# Sheet1_MCU.net
KiCad netlist of a schematic drawn in Altium Designer
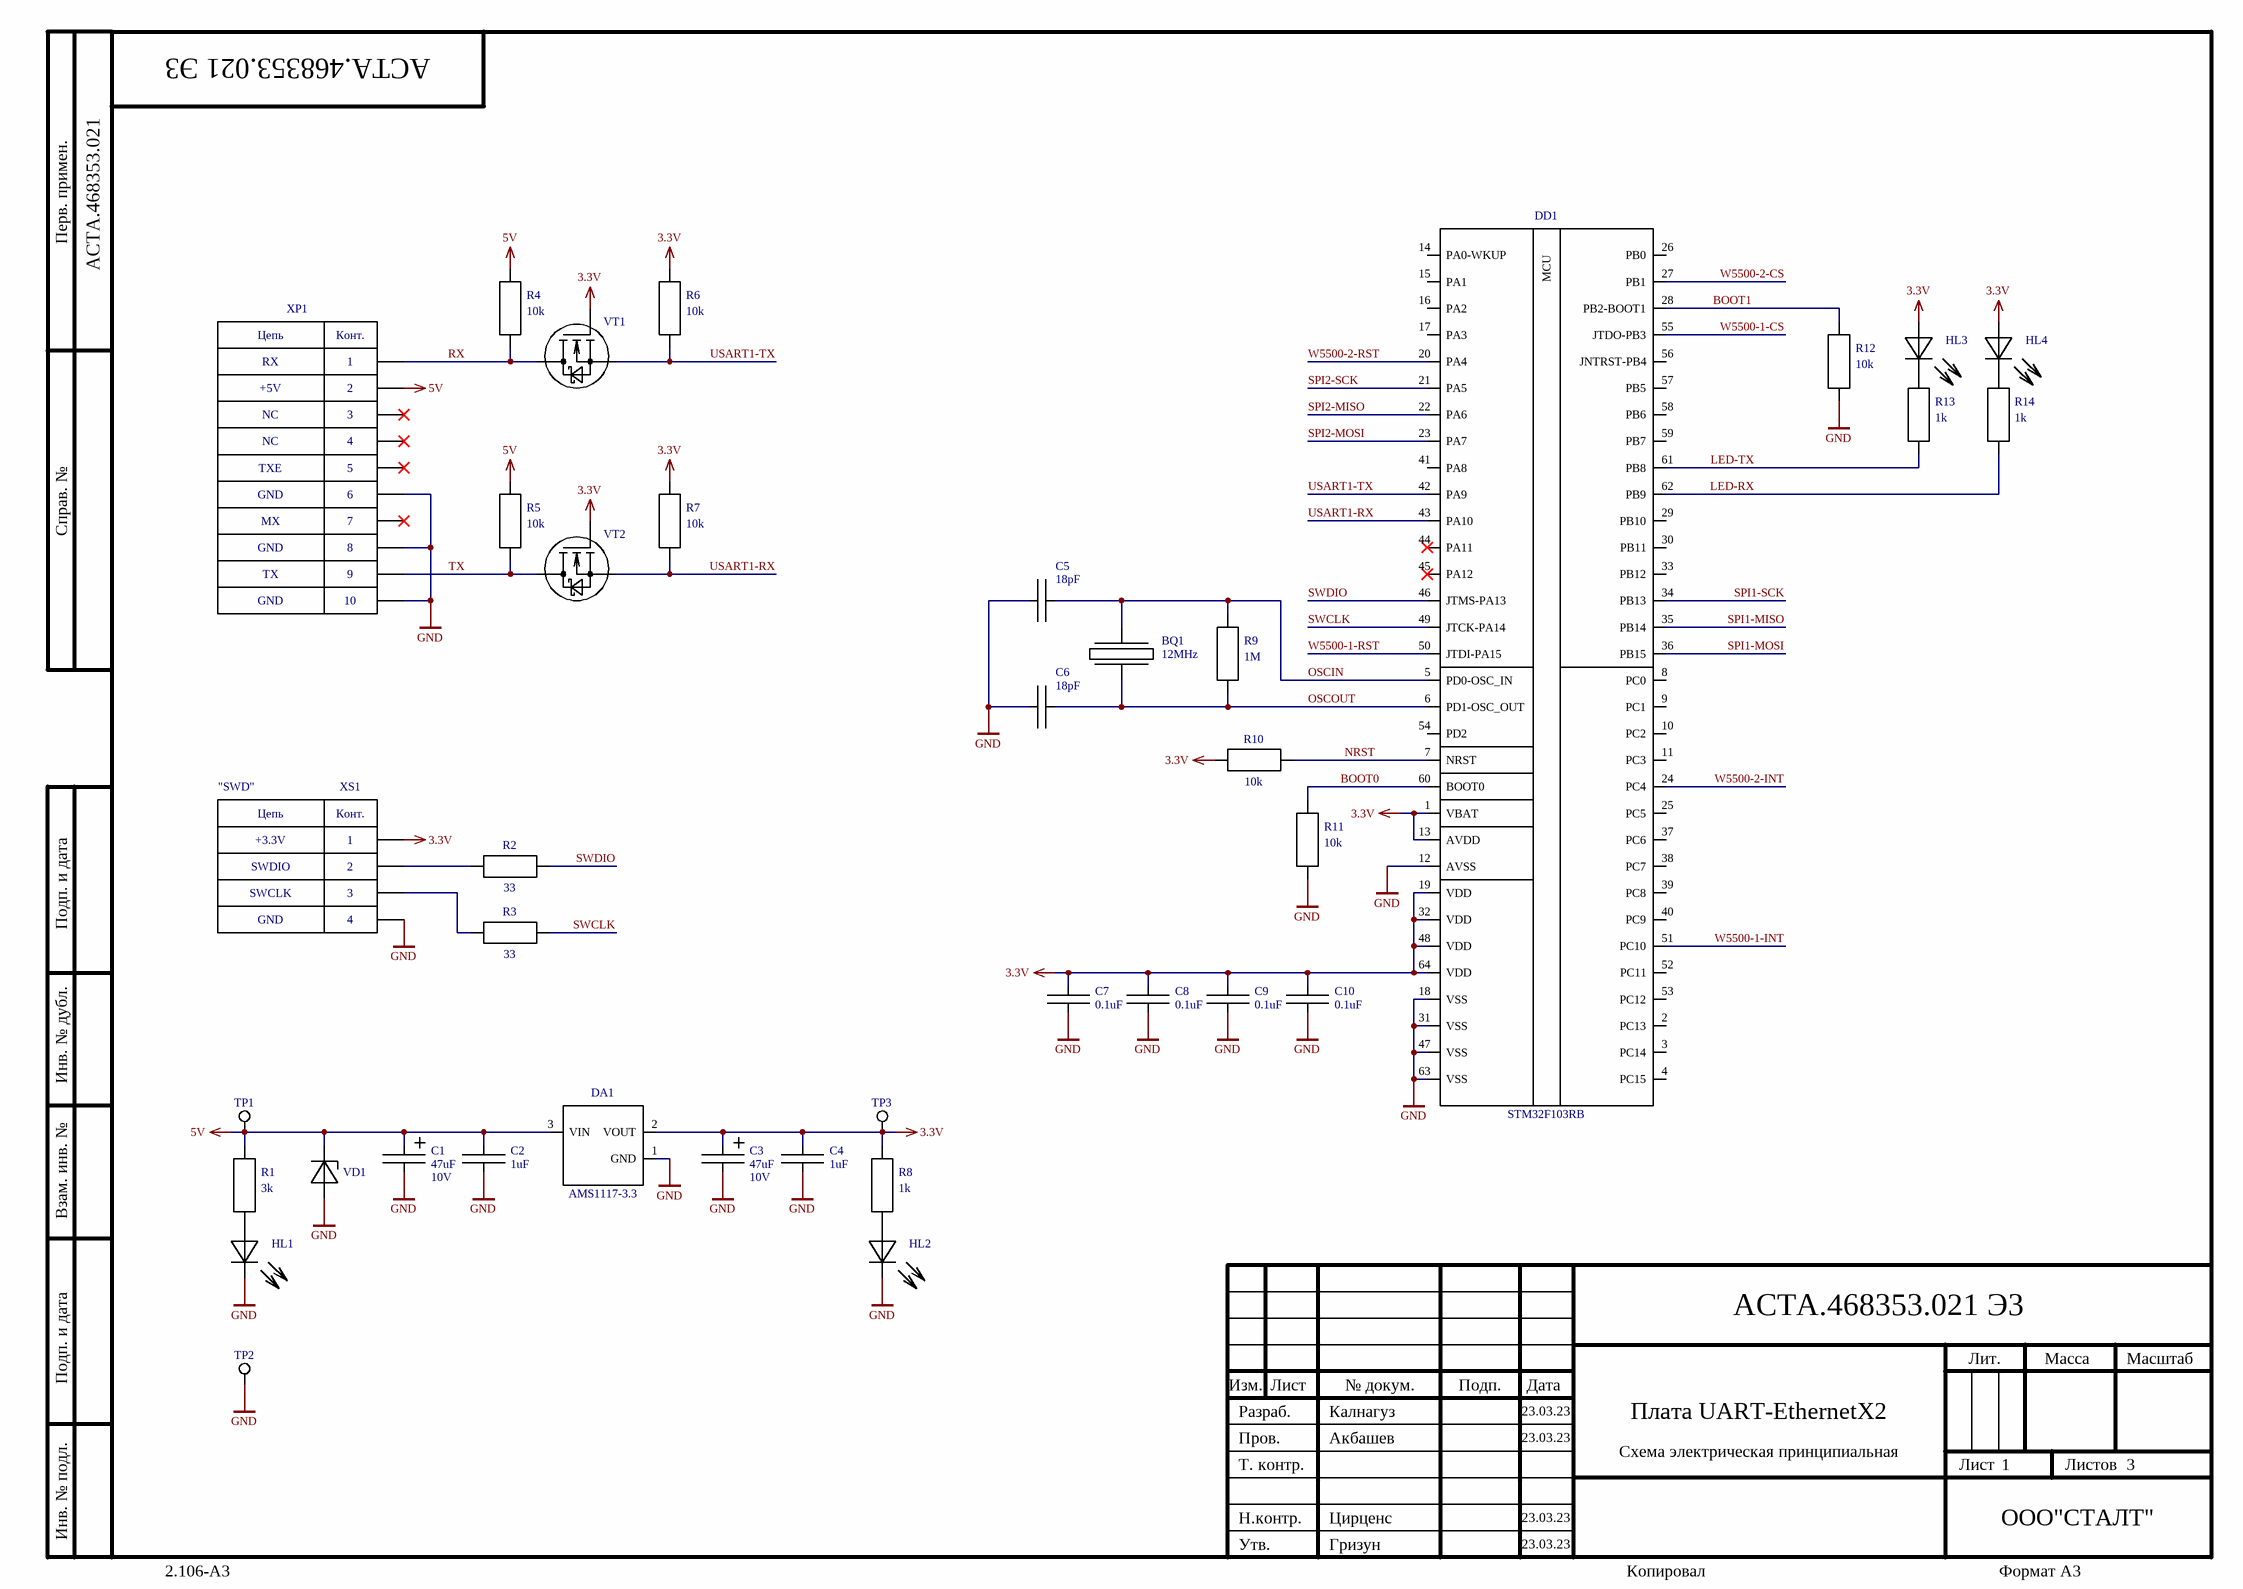
[diagram p0: Sheet1_MCU.SchDoc]

(export (version "E")
  (design (tool "Eeschema 10.0.6"))
  (components
    (comp (ref "BQ1")
      (value "12MHz")
      (footprint "HT-49S")
      (fields (field (name "Comment") "HT-49S_Rated"))
      (libsource (lib "Resonators") (part "HT-49S_Rated"))
    )
    (comp (ref "C1")
      (value "47uF")
      (footprint "CaseB_TantalumCap")
      (fields (field (name "VOLTAGE") "10V") (field (name "Comment") "CaseB_TantalumCap"))
      (libsource (lib "Tantalum_Capacitors") (part "CaseB_TantalumCap"))
    )
    (comp (ref "C2")
      (value "1uF")
      (footprint "CAP0805")
      (fields (field (name "Comment") "CAP0805_Rated"))
      (libsource (lib "Ceramic_Capacitors") (part "CAP0805_Rated"))
    )
    (comp (ref "C3")
      (value "47uF")
      (footprint "CaseB_TantalumCap")
      (fields (field (name "VOLTAGE") "10V") (field (name "Comment") "CaseB_TantalumCap"))
      (libsource (lib "Tantalum_Capacitors") (part "CaseB_TantalumCap"))
    )
    (comp (ref "C4")
      (value "1uF")
      (footprint "CAP0805")
      (fields (field (name "Comment") "CAP0805_Rated"))
      (libsource (lib "Ceramic_Capacitors") (part "CAP0805_Rated"))
    )
    (comp (ref "C5")
      (value "18pF")
      (footprint "CAP0805")
      (fields (field (name "Comment") "CAP0805_Rated"))
      (libsource (lib "Ceramic_Capacitors") (part "CAP0805_Rated"))
    )
    (comp (ref "C6")
      (value "18pF")
      (footprint "CAP0805")
      (fields (field (name "Comment") "CAP0805_Rated"))
      (libsource (lib "Ceramic_Capacitors") (part "CAP0805_Rated"))
    )
    (comp (ref "C7")
      (value "0.1uF")
      (footprint "CAP0805")
      (fields (field (name "Comment") "CAP0805_Rated"))
      (libsource (lib "Ceramic_Capacitors") (part "CAP0805_Rated"))
    )
    (comp (ref "C8")
      (value "0.1uF")
      (footprint "CAP0805")
      (fields (field (name "Comment") "CAP0805_Rated"))
      (libsource (lib "Ceramic_Capacitors") (part "CAP0805_Rated"))
    )
    (comp (ref "C9")
      (value "0.1uF")
      (footprint "CAP0805")
      (fields (field (name "Comment") "CAP0805_Rated"))
      (libsource (lib "Ceramic_Capacitors") (part "CAP0805_Rated"))
    )
    (comp (ref "C10")
      (value "0.1uF")
      (footprint "CAP0805")
      (fields (field (name "Comment") "CAP0805_Rated"))
      (libsource (lib "Ceramic_Capacitors") (part "CAP0805_Rated"))
    )
    (comp (ref "DA1")
      (value "AMS1117-3.3")
      (footprint "SOT-223")
      (description "Fixed Voltage 3.3V 1A Low Dropout Voltage Regulator")
      (libsource (lib "Power_Management_ICs") (part "AMS1117-3.3"))
    )
    (comp (ref "DD1")
      (value "STM32F103RB")
      (footprint "LQFP-64")
      (description "ARM Cortex-M3 MCU")
      (libsource (lib "MCU") (part "STM32F103RB"))
    )
    (comp (ref "HL1")
      (value "KPTD-3216MGC")
      (footprint "KPTD-3216 Green")
      (description "3.2x1.6mm SMD LED Mega Green")
      (libsource (lib "LEDs_SMD") (part "KPTD-3216MGC"))
    )
    (comp (ref "HL2")
      (value "KPTD-3216MGC")
      (footprint "KPTD-3216 Green")
      (description "3.2x1.6mm SMD LED Mega Green")
      (libsource (lib "LEDs_SMD") (part "KPTD-3216MGC"))
    )
    (comp (ref "HL3")
      (value "KPTD-3216MGC")
      (footprint "KPTD-3216 Green")
      (description "3.2x1.6mm SMD LED Mega Green")
      (libsource (lib "LEDs_SMD") (part "KPTD-3216MGC"))
    )
    (comp (ref "HL4")
      (value "KPTD-3216SYC")
      (footprint "KPTD-3216 Yellow")
      (description "3.2x1.6mm SMD LED Super Bright Yellow")
      (libsource (lib "LEDs_SMD") (part "KPTD-3216SYC"))
    )
    (comp (ref "R1")
      (value "3k")
      (footprint "RES0805")
      (fields (field (name "TOLERANCE") "5%") (field (name "Comment") "RES0805_Rated"))
      (libsource (lib "Resistors") (part "RES0805_Rated"))
    )
    (comp (ref "R2")
      (value "33")
      (footprint "RES0805")
      (fields (field (name "TOLERANCE") "5%") (field (name "Comment") "RES0805_Rated"))
      (libsource (lib "") (part "RES0805_Rated_1"))
    )
    (comp (ref "R3")
      (value "33")
      (footprint "RES0805")
      (fields (field (name "TOLERANCE") "5%") (field (name "Comment") "RES0805_Rated"))
      (libsource (lib "") (part "RES0805_Rated_1"))
    )
    (comp (ref "R4")
      (value "10k")
      (footprint "RES0805")
      (fields (field (name "TOLERANCE") "5%") (field (name "Comment") "RES0805_Rated"))
      (libsource (lib "Resistors") (part "RES0805_Rated"))
    )
    (comp (ref "R5")
      (value "10k")
      (footprint "RES0805")
      (fields (field (name "TOLERANCE") "5%") (field (name "Comment") "RES0805_Rated"))
      (libsource (lib "Resistors") (part "RES0805_Rated"))
    )
    (comp (ref "R6")
      (value "10k")
      (footprint "RES0805")
      (fields (field (name "TOLERANCE") "5%") (field (name "Comment") "RES0805_Rated"))
      (libsource (lib "Resistors") (part "RES0805_Rated"))
    )
    (comp (ref "R7")
      (value "10k")
      (footprint "RES0805")
      (fields (field (name "TOLERANCE") "5%") (field (name "Comment") "RES0805_Rated"))
      (libsource (lib "Resistors") (part "RES0805_Rated"))
    )
    (comp (ref "R8")
      (value "1k")
      (footprint "RES0805")
      (fields (field (name "TOLERANCE") "5%") (field (name "Comment") "RES0805_Rated"))
      (libsource (lib "Resistors") (part "RES0805_Rated"))
    )
    (comp (ref "R9")
      (value "1M")
      (footprint "RES0805")
      (fields (field (name "TOLERANCE") "5%") (field (name "Comment") "RES0805_Rated"))
      (libsource (lib "Resistors") (part "RES0805_Rated"))
    )
    (comp (ref "R10")
      (value "10k")
      (footprint "RES0805")
      (fields (field (name "TOLERANCE") "5%") (field (name "Comment") "RES0805_Rated"))
      (libsource (lib "") (part "RES0805_Rated_1"))
    )
    (comp (ref "R11")
      (value "10k")
      (footprint "RES0805")
      (fields (field (name "TOLERANCE") "5%") (field (name "Comment") "RES0805_Rated"))
      (libsource (lib "Resistors") (part "RES0805_Rated"))
    )
    (comp (ref "R12")
      (value "10k")
      (footprint "RES0805")
      (fields (field (name "TOLERANCE") "5%") (field (name "Comment") "RES0805_Rated"))
      (libsource (lib "Resistors") (part "RES0805_Rated"))
    )
    (comp (ref "R13")
      (value "1k")
      (footprint "RES0805")
      (fields (field (name "TOLERANCE") "5%") (field (name "Comment") "RES0805_Rated"))
      (libsource (lib "Resistors") (part "RES0805_Rated"))
    )
    (comp (ref "R14")
      (value "1k")
      (footprint "RES0805")
      (fields (field (name "TOLERANCE") "5%") (field (name "Comment") "RES0805_Rated"))
      (libsource (lib "Resistors") (part "RES0805_Rated"))
    )
    (comp (ref "TP1")
      (value "TestPad")
      (footprint "PAD-TH-OCT1x1-0.5")
      (description "TestPoint on PCB")
      (libsource (lib "Connectors") (part "TestPad"))
    )
    (comp (ref "TP2")
      (value "TestPad")
      (footprint "PAD-TH-OCT1x1-0.5")
      (description "TestPoint on PCB")
      (libsource (lib "Connectors") (part "TestPad"))
    )
    (comp (ref "TP3")
      (value "TestPad")
      (footprint "PAD-TH-OCT1x1-0.5")
      (description "TestPoint on PCB")
      (libsource (lib "Connectors") (part "TestPad"))
    )
    (comp (ref "VD1")
      (value "SMAJ5.0A")
      (footprint "SMA (DO-214AC)")
      (description "5Vr 400W 43.5A UniDirectional TVS")
      (libsource (lib "TVS_Diodes") (part "SMAJ5.0A"))
    )
    (comp (ref "VT1")
      (value "BSS138")
      (footprint "SOT-23")
      (description "Small Signal N-Channel MOSFET 50V 220mA")
      (libsource (lib "MOSFETs") (part "BSS138"))
    )
    (comp (ref "VT2")
      (value "BSS138")
      (footprint "SOT-23")
      (description "Small Signal N-Channel MOSFET 50V 220mA")
      (libsource (lib "MOSFETs") (part "BSS138"))
    )
    (comp (ref "XP1")
      (value "IDC-10MS")
      (footprint "IDC-10MS pad1.6x2.0")
      (description "Box Header Pitch 2.54mm")
      (fields
        (field (name "CIRCUIT7") "MX")
        (field (name "CIRCUIT8") "GND")
        (field (name "CIRCUIT9") "TX")
        (field (name "CIRCUIT10") "GND")
        (field (name "CIRCUIT6") "GND")
        (field (name "CIRCUIT4") "NC")
        (field (name "CIRCUIT5") "TXE")
        (field (name "CIRCUIT3") "NC")
        (field (name "CIRCUIT2") "+5V")
        (field (name "CIRCUIT1") "RX")
      )
      (libsource (lib "Connectors") (part "IDC-10MS"))
    )
    (comp (ref "XS1")
      (value "PBS-4")
      (footprint "PBS-4")
      (description "Female Header Pitch 2.54mm")
      (fields
        (field (name "CIRCUIT4") "GND")
        (field (name "CIRCUIT3") "SWCLK")
        (field (name "CIRCUIT1") "+3.3V")
        (field (name "CIRCUIT2") "SWDIO")
        (field (name "LABEL") "\"SWD\"")
      )
      (libsource (lib "Connectors") (part "PBS-4"))
    )
  )
  (nets
    (net (code "1") (name "/BOOT0") (class "Default")
      (node (ref "DD1") (pin "60") (pinfunction "BOOT0_60") (pintype "power_in"))
      (node (ref "R11") (pin "2") (pinfunction "2_2") (pintype "passive"))
    )
    (net (code "2") (name "/BOOT1") (class "Default")
      (node (ref "DD1") (pin "28") (pinfunction "PB2-BOOT1_28") (pintype "bidirectional"))
      (node (ref "R12") (pin "2") (pinfunction "2_2") (pintype "passive"))
    )
    (net (code "3") (name "/LED-RX") (class "Default")
      (node (ref "DD1") (pin "62") (pinfunction "PB9_62") (pintype "bidirectional"))
      (node (ref "R14") (pin "1") (pinfunction "1_1") (pintype "passive"))
    )
    (net (code "4") (name "/LED-TX") (class "Default")
      (node (ref "DD1") (pin "61") (pinfunction "PB8_61") (pintype "bidirectional"))
      (node (ref "R13") (pin "1") (pinfunction "1_1") (pintype "passive"))
    )
    (net (code "5") (name "/NRST") (class "Default")
      (node (ref "DD1") (pin "7") (pinfunction "NRST_7") (pintype "bidirectional"))
      (node (ref "R10") (pin "2") (pinfunction "2_2") (pintype "passive"))
    )
    (net (code "6") (name "/OSCIN") (class "Default")
      (node (ref "BQ1") (pin "1") (pinfunction "1_1") (pintype "passive"))
      (node (ref "C5") (pin "2") (pinfunction "2_2") (pintype "passive"))
      (node (ref "DD1") (pin "5") (pinfunction "PD0-OSC_IN_5") (pintype "bidirectional"))
      (node (ref "R9") (pin "2") (pinfunction "2_2") (pintype "passive"))
    )
    (net (code "7") (name "/OSCOUT") (class "Default")
      (node (ref "BQ1") (pin "2") (pinfunction "2_2") (pintype "passive"))
      (node (ref "C6") (pin "2") (pinfunction "2_2") (pintype "passive"))
      (node (ref "DD1") (pin "6") (pinfunction "PD1-OSC_OUT_6") (pintype "bidirectional"))
      (node (ref "R9") (pin "1") (pinfunction "1_1") (pintype "passive"))
    )
    (net (code "8") (name "/RX") (class "Default")
      (node (ref "R4") (pin "1") (pinfunction "1_1") (pintype "passive"))
      (node (ref "VT1") (pin "2") (pinfunction "D_2") (pintype "passive"))
      (node (ref "XP1") (pin "1") (pinfunction "1_1") (pintype "passive"))
    )
    (net (code "9") (name "/SPI1-MISO") (class "Default")
      (node (ref "DD1") (pin "35") (pinfunction "PB14_35") (pintype "bidirectional"))
    )
    (net (code "10") (name "/SPI1-MOSI") (class "Default")
      (node (ref "DD1") (pin "36") (pinfunction "PB15_36") (pintype "bidirectional"))
    )
    (net (code "11") (name "/SPI1-SCK") (class "Default")
      (node (ref "DD1") (pin "34") (pinfunction "PB13_34") (pintype "bidirectional"))
    )
    (net (code "12") (name "/SPI2-MISO") (class "Default")
      (node (ref "DD1") (pin "22") (pinfunction "PA6_22") (pintype "bidirectional"))
    )
    (net (code "13") (name "/SPI2-MOSI") (class "Default")
      (node (ref "DD1") (pin "23") (pinfunction "PA7_23") (pintype "bidirectional"))
    )
    (net (code "14") (name "/SPI2-SCK") (class "Default")
      (node (ref "DD1") (pin "21") (pinfunction "PA5_21") (pintype "bidirectional"))
    )
    (net (code "15") (name "/SWCLK") (class "Default")
      (node (ref "DD1") (pin "49") (pinfunction "JTCK-PA14_49") (pintype "bidirectional"))
      (node (ref "R3") (pin "2") (pinfunction "2_2") (pintype "passive"))
    )
    (net (code "16") (name "/SWDIO") (class "Default")
      (node (ref "DD1") (pin "46") (pinfunction "JTMS-PA13_46") (pintype "bidirectional"))
      (node (ref "R2") (pin "2") (pinfunction "2_2") (pintype "passive"))
    )
    (net (code "17") (name "/TX") (class "Default")
      (node (ref "R5") (pin "1") (pinfunction "1_1") (pintype "passive"))
      (node (ref "VT2") (pin "2") (pinfunction "D_2") (pintype "passive"))
      (node (ref "XP1") (pin "9") (pinfunction "9_9") (pintype "passive"))
    )
    (net (code "18") (name "/USART1-RX") (class "Default")
      (node (ref "DD1") (pin "43") (pinfunction "PA10_43") (pintype "bidirectional"))
      (node (ref "R7") (pin "1") (pinfunction "1_1") (pintype "passive"))
      (node (ref "VT2") (pin "3") (pinfunction "S_3") (pintype "passive"))
    )
    (net (code "19") (name "/USART1-TX") (class "Default")
      (node (ref "DD1") (pin "42") (pinfunction "PA9_42") (pintype "bidirectional"))
      (node (ref "R6") (pin "1") (pinfunction "1_1") (pintype "passive"))
      (node (ref "VT1") (pin "3") (pinfunction "S_3") (pintype "passive"))
    )
    (net (code "20") (name "/W5500-1-CS") (class "Default")
      (node (ref "DD1") (pin "55") (pinfunction "JTDO-PB3_55") (pintype "bidirectional"))
    )
    (net (code "21") (name "/W5500-1-INT") (class "Default")
      (node (ref "DD1") (pin "51") (pinfunction "PC10_51") (pintype "bidirectional"))
    )
    (net (code "22") (name "/W5500-1-RST") (class "Default")
      (node (ref "DD1") (pin "50") (pinfunction "JTDI-PA15_50") (pintype "bidirectional"))
    )
    (net (code "23") (name "/W5500-2-CS") (class "Default")
      (node (ref "DD1") (pin "27") (pinfunction "PB1_27") (pintype "bidirectional"))
    )
    (net (code "24") (name "/W5500-2-INT") (class "Default")
      (node (ref "DD1") (pin "24") (pinfunction "PC4_24") (pintype "bidirectional"))
    )
    (net (code "25") (name "/W5500-2-RST") (class "Default")
      (node (ref "DD1") (pin "20") (pinfunction "PA4_20") (pintype "bidirectional"))
    )
    (net (code "26") (name "3.3V") (class "Default")
      (node (ref "C10") (pin "1") (pinfunction "1_1") (pintype "passive"))
      (node (ref "C3") (pin "1") (pinfunction "+_1") (pintype "passive"))
      (node (ref "C4") (pin "1") (pinfunction "1_1") (pintype "passive"))
      (node (ref "C7") (pin "1") (pinfunction "1_1") (pintype "passive"))
      (node (ref "C8") (pin "1") (pinfunction "1_1") (pintype "passive"))
      (node (ref "C9") (pin "1") (pinfunction "1_1") (pintype "passive"))
      (node (ref "DA1") (pin "2") (pinfunction "VOUT_2") (pintype "power_in"))
      (node (ref "DD1") (pin "1") (pinfunction "VBAT_1") (pintype "power_in"))
      (node (ref "DD1") (pin "13") (pinfunction "AVDD_13") (pintype "power_in"))
      (node (ref "DD1") (pin "19") (pinfunction "VDD_19") (pintype "power_in"))
      (node (ref "DD1") (pin "32") (pinfunction "VDD_32") (pintype "power_in"))
      (node (ref "DD1") (pin "48") (pinfunction "VDD_48") (pintype "power_in"))
      (node (ref "DD1") (pin "64") (pinfunction "VDD_64") (pintype "power_in"))
      (node (ref "HL3") (pin "A") (pinfunction "A_A") (pintype "passive"))
      (node (ref "HL4") (pin "A") (pinfunction "A_A") (pintype "passive"))
      (node (ref "R10") (pin "1") (pinfunction "1_1") (pintype "passive"))
      (node (ref "R6") (pin "2") (pinfunction "2_2") (pintype "passive"))
      (node (ref "R7") (pin "2") (pinfunction "2_2") (pintype "passive"))
      (node (ref "R8") (pin "2") (pinfunction "2_2") (pintype "passive"))
      (node (ref "TP3") (pin "1") (pinfunction "1_1") (pintype "passive"))
      (node (ref "VT1") (pin "1") (pinfunction "G_1") (pintype "passive"))
      (node (ref "VT2") (pin "1") (pinfunction "G_1") (pintype "passive"))
      (node (ref "XS1") (pin "1") (pinfunction "1_1") (pintype "passive"))
    )
    (net (code "27") (name "5V") (class "Default")
      (node (ref "C1") (pin "1") (pinfunction "+_1") (pintype "passive"))
      (node (ref "C2") (pin "1") (pinfunction "1_1") (pintype "passive"))
      (node (ref "DA1") (pin "3") (pinfunction "VIN_3") (pintype "power_in"))
      (node (ref "R1") (pin "2") (pinfunction "2_2") (pintype "passive"))
      (node (ref "R4") (pin "2") (pinfunction "2_2") (pintype "passive"))
      (node (ref "R5") (pin "2") (pinfunction "2_2") (pintype "passive"))
      (node (ref "TP1") (pin "1") (pinfunction "1_1") (pintype "passive"))
      (node (ref "VD1") (pin "K") (pinfunction "K_K") (pintype "passive"))
      (node (ref "XP1") (pin "2") (pinfunction "2_2") (pintype "passive"))
    )
    (net (code "28") (name "GND") (class "Default")
      (node (ref "C1") (pin "2") (pinfunction "-_2") (pintype "passive"))
      (node (ref "C10") (pin "2") (pinfunction "2_2") (pintype "passive"))
      (node (ref "C2") (pin "2") (pinfunction "2_2") (pintype "passive"))
      (node (ref "C3") (pin "2") (pinfunction "-_2") (pintype "passive"))
      (node (ref "C4") (pin "2") (pinfunction "2_2") (pintype "passive"))
      (node (ref "C5") (pin "1") (pinfunction "1_1") (pintype "passive"))
      (node (ref "C6") (pin "1") (pinfunction "1_1") (pintype "passive"))
      (node (ref "C7") (pin "2") (pinfunction "2_2") (pintype "passive"))
      (node (ref "C8") (pin "2") (pinfunction "2_2") (pintype "passive"))
      (node (ref "C9") (pin "2") (pinfunction "2_2") (pintype "passive"))
      (node (ref "DA1") (pin "1") (pinfunction "GND_1") (pintype "power_in"))
      (node (ref "DD1") (pin "12") (pinfunction "AVSS_12") (pintype "power_in"))
      (node (ref "DD1") (pin "18") (pinfunction "VSS_18") (pintype "power_in"))
      (node (ref "DD1") (pin "31") (pinfunction "VSS_31") (pintype "power_in"))
      (node (ref "DD1") (pin "47") (pinfunction "VSS_47") (pintype "power_in"))
      (node (ref "DD1") (pin "63") (pinfunction "VSS_63") (pintype "power_in"))
      (node (ref "HL1") (pin "K") (pinfunction "K_K") (pintype "passive"))
      (node (ref "HL2") (pin "K") (pinfunction "K_K") (pintype "passive"))
      (node (ref "R11") (pin "1") (pinfunction "1_1") (pintype "passive"))
      (node (ref "R12") (pin "1") (pinfunction "1_1") (pintype "passive"))
      (node (ref "TP2") (pin "1") (pinfunction "1_1") (pintype "passive"))
      (node (ref "VD1") (pin "A") (pinfunction "A_A") (pintype "passive"))
      (node (ref "XP1") (pin "10") (pinfunction "10_10") (pintype "passive"))
      (node (ref "XP1") (pin "6") (pinfunction "6_6") (pintype "passive"))
      (node (ref "XP1") (pin "8") (pinfunction "8_8") (pintype "passive"))
      (node (ref "XS1") (pin "4") (pinfunction "4_4") (pintype "passive"))
    )
    (net (code "29") (name "Net-(HL1-PadA)") (class "Default")
      (node (ref "HL1") (pin "A") (pinfunction "A_A") (pintype "passive"))
      (node (ref "R1") (pin "1") (pinfunction "1_1") (pintype "passive"))
    )
    (net (code "30") (name "Net-(HL2-PadA)") (class "Default")
      (node (ref "HL2") (pin "A") (pinfunction "A_A") (pintype "passive"))
      (node (ref "R8") (pin "1") (pinfunction "1_1") (pintype "passive"))
    )
    (net (code "31") (name "Net-(HL3-PadK)") (class "Default")
      (node (ref "HL3") (pin "K") (pinfunction "K_K") (pintype "passive"))
      (node (ref "R13") (pin "2") (pinfunction "2_2") (pintype "passive"))
    )
    (net (code "32") (name "Net-(HL4-PadK)") (class "Default")
      (node (ref "HL4") (pin "K") (pinfunction "K_K") (pintype "passive"))
      (node (ref "R14") (pin "2") (pinfunction "2_2") (pintype "passive"))
    )
    (net (code "33") (name "Net-(R2-Pad1)") (class "Default")
      (node (ref "R2") (pin "1") (pinfunction "1_1") (pintype "passive"))
      (node (ref "XS1") (pin "2") (pinfunction "2_2") (pintype "passive"))
    )
    (net (code "34") (name "Net-(R3-Pad1)") (class "Default")
      (node (ref "R3") (pin "1") (pinfunction "1_1") (pintype "passive"))
      (node (ref "XS1") (pin "3") (pinfunction "3_3") (pintype "passive"))
    )
    (net (code "35") (name "unconnected-(DD1-JNTRST-PB4-Pad56)") (class "Default")
      (node (ref "DD1") (pin "56") (pinfunction "JNTRST-PB4_56") (pintype "bidirectional"))
    )
    (net (code "36") (name "unconnected-(DD1-PA0-WKUP-Pad14)") (class "Default")
      (node (ref "DD1") (pin "14") (pinfunction "PA0-WKUP_14") (pintype "bidirectional"))
    )
    (net (code "37") (name "unconnected-(DD1-PA1-Pad15)") (class "Default")
      (node (ref "DD1") (pin "15") (pinfunction "PA1_15") (pintype "bidirectional"))
    )
    (net (code "38") (name "unconnected-(DD1-PA2-Pad16)") (class "Default")
      (node (ref "DD1") (pin "16") (pinfunction "PA2_16") (pintype "bidirectional"))
    )
    (net (code "39") (name "unconnected-(DD1-PA3-Pad17)") (class "Default")
      (node (ref "DD1") (pin "17") (pinfunction "PA3_17") (pintype "bidirectional"))
    )
    (net (code "40") (name "unconnected-(DD1-PA8-Pad41)") (class "Default")
      (node (ref "DD1") (pin "41") (pinfunction "PA8_41") (pintype "bidirectional"))
    )
    (net (code "41") (name "unconnected-(DD1-PA11-Pad44)") (class "Default")
      (node (ref "DD1") (pin "44") (pinfunction "PA11_44") (pintype "bidirectional+no_connect"))
    )
    (net (code "42") (name "unconnected-(DD1-PA12-Pad45)") (class "Default")
      (node (ref "DD1") (pin "45") (pinfunction "PA12_45") (pintype "bidirectional+no_connect"))
    )
    (net (code "43") (name "unconnected-(DD1-PB0-Pad26)") (class "Default")
      (node (ref "DD1") (pin "26") (pinfunction "PB0_26") (pintype "bidirectional"))
    )
    (net (code "44") (name "unconnected-(DD1-PB5-Pad57)") (class "Default")
      (node (ref "DD1") (pin "57") (pinfunction "PB5_57") (pintype "bidirectional"))
    )
    (net (code "45") (name "unconnected-(DD1-PB6-Pad58)") (class "Default")
      (node (ref "DD1") (pin "58") (pinfunction "PB6_58") (pintype "bidirectional"))
    )
    (net (code "46") (name "unconnected-(DD1-PB7-Pad59)") (class "Default")
      (node (ref "DD1") (pin "59") (pinfunction "PB7_59") (pintype "bidirectional"))
    )
    (net (code "47") (name "unconnected-(DD1-PB10-Pad29)") (class "Default")
      (node (ref "DD1") (pin "29") (pinfunction "PB10_29") (pintype "bidirectional"))
    )
    (net (code "48") (name "unconnected-(DD1-PB11-Pad30)") (class "Default")
      (node (ref "DD1") (pin "30") (pinfunction "PB11_30") (pintype "bidirectional"))
    )
    (net (code "49") (name "unconnected-(DD1-PB12-Pad33)") (class "Default")
      (node (ref "DD1") (pin "33") (pinfunction "PB12_33") (pintype "bidirectional"))
    )
    (net (code "50") (name "unconnected-(DD1-PC0-Pad8)") (class "Default")
      (node (ref "DD1") (pin "8") (pinfunction "PC0_8") (pintype "bidirectional"))
    )
    (net (code "51") (name "unconnected-(DD1-PC1-Pad9)") (class "Default")
      (node (ref "DD1") (pin "9") (pinfunction "PC1_9") (pintype "bidirectional"))
    )
    (net (code "52") (name "unconnected-(DD1-PC2-Pad10)") (class "Default")
      (node (ref "DD1") (pin "10") (pinfunction "PC2_10") (pintype "bidirectional"))
    )
    (net (code "53") (name "unconnected-(DD1-PC3-Pad11)") (class "Default")
      (node (ref "DD1") (pin "11") (pinfunction "PC3_11") (pintype "bidirectional"))
    )
    (net (code "54") (name "unconnected-(DD1-PC5-Pad25)") (class "Default")
      (node (ref "DD1") (pin "25") (pinfunction "PC5_25") (pintype "bidirectional"))
    )
    (net (code "55") (name "unconnected-(DD1-PC6-Pad37)") (class "Default")
      (node (ref "DD1") (pin "37") (pinfunction "PC6_37") (pintype "bidirectional"))
    )
    (net (code "56") (name "unconnected-(DD1-PC7-Pad38)") (class "Default")
      (node (ref "DD1") (pin "38") (pinfunction "PC7_38") (pintype "bidirectional"))
    )
    (net (code "57") (name "unconnected-(DD1-PC8-Pad39)") (class "Default")
      (node (ref "DD1") (pin "39") (pinfunction "PC8_39") (pintype "bidirectional"))
    )
    (net (code "58") (name "unconnected-(DD1-PC9-Pad40)") (class "Default")
      (node (ref "DD1") (pin "40") (pinfunction "PC9_40") (pintype "bidirectional"))
    )
    (net (code "59") (name "unconnected-(DD1-PC11-Pad52)") (class "Default")
      (node (ref "DD1") (pin "52") (pinfunction "PC11_52") (pintype "bidirectional"))
    )
    (net (code "60") (name "unconnected-(DD1-PC12-Pad53)") (class "Default")
      (node (ref "DD1") (pin "53") (pinfunction "PC12_53") (pintype "bidirectional"))
    )
    (net (code "61") (name "unconnected-(DD1-PC13-Pad2)") (class "Default")
      (node (ref "DD1") (pin "2") (pinfunction "PC13_2") (pintype "bidirectional"))
    )
    (net (code "62") (name "unconnected-(DD1-PC14-Pad3)") (class "Default")
      (node (ref "DD1") (pin "3") (pinfunction "PC14_3") (pintype "bidirectional"))
    )
    (net (code "63") (name "unconnected-(DD1-PC15-Pad4)") (class "Default")
      (node (ref "DD1") (pin "4") (pinfunction "PC15_4") (pintype "bidirectional"))
    )
    (net (code "64") (name "unconnected-(DD1-PD2-Pad54)") (class "Default")
      (node (ref "DD1") (pin "54") (pinfunction "PD2_54") (pintype "bidirectional"))
    )
    (net (code "65") (name "unconnected-(XP1-Pad3)") (class "Default")
      (node (ref "XP1") (pin "3") (pinfunction "3_3") (pintype "passive+no_connect"))
    )
    (net (code "66") (name "unconnected-(XP1-Pad4)") (class "Default")
      (node (ref "XP1") (pin "4") (pinfunction "4_4") (pintype "passive+no_connect"))
    )
    (net (code "67") (name "unconnected-(XP1-Pad5)") (class "Default")
      (node (ref "XP1") (pin "5") (pinfunction "5_5") (pintype "passive+no_connect"))
    )
    (net (code "68") (name "unconnected-(XP1-Pad7)") (class "Default")
      (node (ref "XP1") (pin "7") (pinfunction "7_7") (pintype "passive+no_connect"))
    )
  )
)
